# chicker.net
KiCad netlist of a schematic drawn in Altium Designer
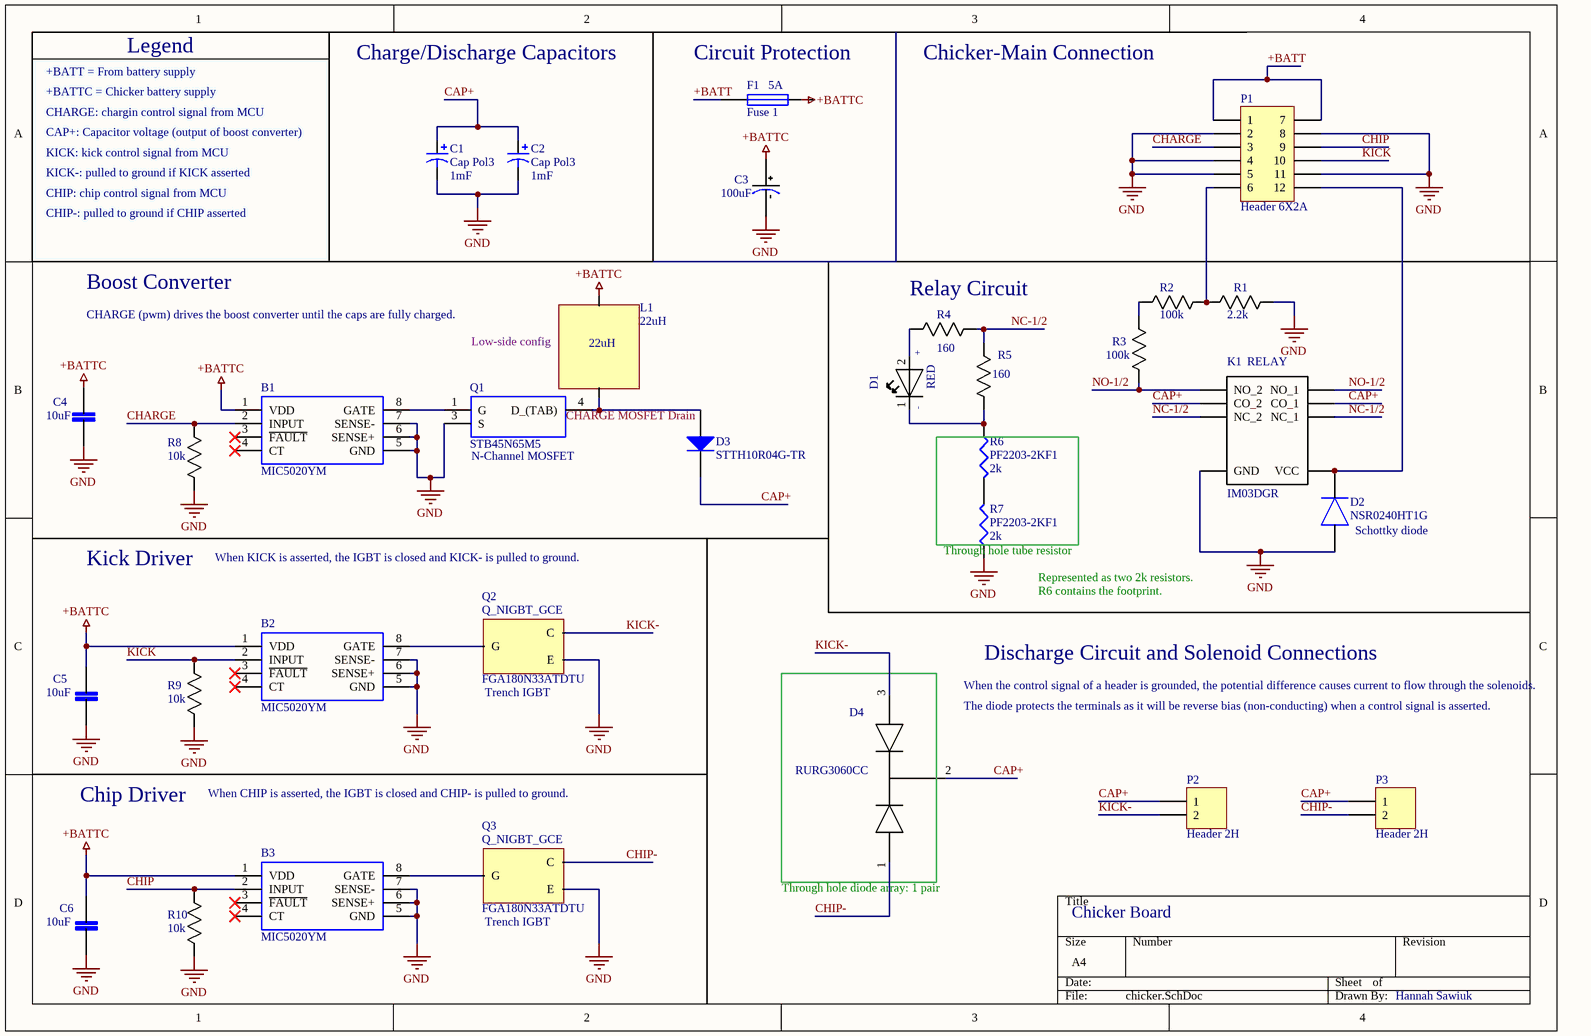
[diagram p0: chicker.SchDoc]

(export (version "E")
  (design (tool "Eeschema 10.0.6"))
  (components
    (comp (ref "B1")
      (value "MIC5020YM")
      (footprint "SOIC127P600X188-8N")
      (description "Low-Side Gate Driver IC Non-Inverting 8-SOIC")
      (fields (field (name "MP") "Microchip") (field (name "DIGI-KEY_PART_NUM") "576-1818-5-ND"))
      (libsource (lib "MIC5020YM") (part "MIC5020YM"))
    )
    (comp (ref "B2")
      (value "MIC5020YM")
      (footprint "SOIC127P600X188-8N")
      (description "Low-Side Gate Driver IC Non-Inverting 8-SOIC")
      (fields (field (name "MP") "Microchip") (field (name "DIGI-KEY_PART_NUM") "576-1818-5-ND"))
      (libsource (lib "MIC5020YM") (part "MIC5020YM"))
    )
    (comp (ref "B3")
      (value "MIC5020YM")
      (footprint "SOIC127P600X188-8N")
      (description "Low-Side Gate Driver IC Non-Inverting 8-SOIC")
      (fields (field (name "MP") "Microchip") (field (name "DIGI-KEY_PART_NUM") "576-1818-5-ND"))
      (libsource (lib "MIC5020YM") (part "MIC5020YM"))
    )
    (comp (ref "C1")
      (value "Cap Pol3")
      (footprint "C0805")
      (description "Polarized Capacitor (Surface Mount)")
      (fields
        (field (name "ALTIUM_VALUE") "1mF")
        (field (name "DIGI-KEY_PART_NUM") "565-2754-ND")
        (field (name "MF") "United Chemi-Con")
      )
      (libsource (lib "Miscellaneous Devices") (part "Cap Pol3"))
    )
    (comp (ref "C2")
      (value "Cap Pol3")
      (footprint "C0805")
      (description "Polarized Capacitor (Surface Mount)")
      (fields
        (field (name "ALTIUM_VALUE") "1mF")
        (field (name "DIGI-KEY_PART_NUM") "565-2754-ND")
        (field (name "MF") "United Chemi-Con")
      )
      (libsource (lib "Miscellaneous Devices") (part "Cap Pol3"))
    )
    (comp (ref "C3")
      (value "100uF")
      (footprint "CAPPRD350W60D800H1150B_ECA-1HM101(Primary)")
      (description "CAP ALUM 100UF 20% 50V RADIAL")
      (fields (field (name "MF") "Panasonic") (field (name "MP") "ECA-1HM101"))
      (libsource (lib "ECA-1HM101") (part "ECA-1HM101"))
    )
    (comp (ref "C4")
      (value "10uF")
      (footprint "CAPC3216X100N")
      (description "CAP CER 10UF 25V X5R 1206")
      (fields (field (name "MF") "Samsung") (field (name "MP") "CL31A106KAHNNNE"))
      (libsource (lib "") (part "CL31A226KOCLFNC_1"))
    )
    (comp (ref "C5")
      (value "10uF")
      (footprint "CAPC3216X100N")
      (description "CAP CER 10UF 25V X5R 1206")
      (fields (field (name "MF") "Samsung") (field (name "MP") "CL31A106KAHNNNE"))
      (libsource (lib "CL31A226KOCLFNC") (part "CL31A226KOCLFNC"))
    )
    (comp (ref "C6")
      (value "10uF")
      (footprint "CAPC3216X100N")
      (description "CAP CER 10UF 25V X5R 1206")
      (fields (field (name "MF") "Samsung") (field (name "MP") "CL31A106KAHNNNE"))
      (libsource (lib "CL31A226KOCLFNC") (part "CL31A226KOCLFNC"))
    )
    (comp (ref "D1")
      (value "RED")
      (footprint "WL-SMRW-1206-RECT")
      (description "LED RED CLEAR 1206 SMD")
      (fields (field (name "MF") "Lite-On Inc.") (field (name "MP") "LTST-C150CKT"))
      (libsource (lib "WL-SMRW") (part "WL-SMRW"))
    )
    (comp (ref "D2")
      (value "NSR0240HT1G")
      (footprint "SOD2512X110N")
      (description "SMT Schottky Diode, 40V dc 250mA, 3ns, 2-pin SOD-323")
      (fields (field (name "MF") "ON Semiconductor") (field (name "RS PART NUMBER") "7931024P"))
      (libsource (lib "NSR0240HT1G") (part "NSR0240HT1G"))
    )
    (comp (ref "D3")
      (value "STTH10R04G-TR")
      (footprint "DPAK508P1542X460-3N")
      (description "DIODE GEN PURP 400V 10A D2PAK")
      (fields (field (name "DIGI-KEY_PART_NUM") "497-7575-1-ND") (field (name "MF") "STMicroelectronics"))
      (libsource (lib "Miscellaneous Devices") (part "Diode 1N914"))
    )
    (comp (ref "D4")
      (value "RURG3060CC")
      (footprint "SOT93_TIP147(Primary)")
      (description "DIODE ARRAY GP 600V 30A TO247")
      (fields (field (name "DIGI-KEY_PART_NUM") "RURG3060CC-ND") (field (name "MF") "On Semiconductor"))
      (libsource (lib "Schematic Components") (part "RURG3060CC"))
    )
    (comp (ref "F1")
      (value "Fuse 1")
      (footprint "FUSM3216X140N")
      (description "FUSE BOARD MOUNT 5A 32VDC 1206")
      (fields (field (name "DIGI-KEY_PART_NUM") "F3539CT-ND") (field (name "MF") "Littelfuse Inc."))
      (libsource (lib "Miscellaneous Devices") (part "Fuse 1"))
    )
    (comp (ref "K1")
      (value "IM03DGR")
      (footprint "GULLWINGS")
      (description "Relay, Signal, Dpdt, 250vac, 220vdc, 5a")
      (fields
        (field (name "MF") "TE Connectivity")
        (field (name "ALTIUM_VALUE") "RELAY")
        (field (name "MOUSER_PART_NUM") "655-IM03DGR")
      )
      (libsource (lib "IM03DGR") (part "IM03DGR"))
    )
    (comp (ref "L1")
      (value "22uH")
      (footprint "PCBComponent_1")
      (libsource (lib "Schematic Components") (part "Inductor 22uH"))
    )
    (comp (ref "P1")
      (value "Header 6X2A")
      (footprint "HDR2X6_CEN")
      (description "Header, 6-Pin, Dual row")
      (fields
        (field (name "DIGI-KEY_PART_NUM") "S2011E-06-ND")
        (field (name "MF") "Sullins Connector Solutions")
        (field (name "PUBLISHER") "Altium Limited")
      )
      (libsource (lib "Miscellaneous Connectors") (part "Header 6X2A"))
    )
    (comp (ref "P2")
      (value "Header 2H")
      (footprint "HDR1X2H")
      (description "2 Positions Header Connector 0.100\" (2.54mm) Through Hole, Right Angle Tin")
      (fields (field (name "DIGI-KEY_PART_NUM") "WM4300-ND") (field (name "MF") "Molex, LLC"))
      (libsource (lib "Miscellaneous Connectors") (part "Header 2H"))
    )
    (comp (ref "P3")
      (value "Header 2H")
      (footprint "HDR1X2H")
      (description "2 Positions Header Connector 0.100\" (2.54mm) Through Hole, Right Angle Tin")
      (fields (field (name "DIGI-KEY_PART_NUM") "WM4300-ND") (field (name "MF") "Molex, LLC"))
      (libsource (lib "Miscellaneous Connectors") (part "Header 2H"))
    )
    (comp (ref "Q1")
      (value "STB45N65M5")
      (footprint "TO254P1542X460-3N")
      (description "MOSFET N CH 650V 35A D2PAK")
      (fields (field (name "MF") "STMicroelectronics") (field (name "DIGI-KEY_PART_NUM") "497-12940-1-ND"))
      (libsource (lib "STB45N65M5") (part "STB45N65M5"))
    )
    (comp (ref "Q2")
      (value "FGA180N33ATDTU")
      (footprint "TO-3PN_V_FDA69N25(Primary)")
      (description "IGBT Trench 330V 180A 390W Through Hole TO-3P")
      (fields (field (name "DIGI-KEY_PART_NUM") "FGA180N33ATDTU-ND") (field (name "MF") "ON Semiconductor"))
      (libsource (lib "Schematic Components") (part "FGA180N33ATDTU"))
    )
    (comp (ref "Q3")
      (value "FGA180N33ATDTU")
      (footprint "TO-3PN_V_FDA69N25(Primary)")
      (description "IGBT Trench 330V 180A 390W Through Hole TO-3P")
      (fields (field (name "DIGI-KEY_PART_NUM") "FGA180N33ATDTU-ND") (field (name "MF") "ON Semiconductor"))
      (libsource (lib "Schematic Components") (part "FGA180N33ATDTU"))
    )
    (comp (ref "R1")
      (value "2.2k")
      (footprint "RESC2013X65N")
      (description "RES SMD 2.2K OHM 1% 1/8W 0805")
      (fields (field (name "MP") "RC0805FR-072K2L") (field (name "MF") "Yageo"))
      (libsource (lib "RC0805FR-072K2L") (part "RC0805FR-072K2L"))
    )
    (comp (ref "R2")
      (value "100k")
      (footprint "RESC2013X65N")
      (description "RES SMD 100K OHM 1% 1/8W 0805")
      (fields (field (name "MP") "RC0805FR-07100KL") (field (name "MF") "Yageo"))
      (libsource (lib "RC0805FR-072K2L") (part "RC0805FR-072K2L"))
    )
    (comp (ref "R3")
      (value "100k")
      (footprint "RESC2013X65N")
      (description "RES SMD 100K OHM 1% 1/8W 0805")
      (fields (field (name "MP") "RC0805FR-07100KL") (field (name "MF") "Yageo"))
      (libsource (lib "RC0805FR-072K2L") (part "RC0805FR-072K2L"))
    )
    (comp (ref "R4")
      (value "160")
      (footprint "RESC2013X65N")
      (description "RES SMD 160 OHM 1% 1/8W 0805")
      (fields (field (name "MP") "RC0805FR-07160RL") (field (name "MF") "Yageo"))
      (libsource (lib "RC0805FR-072K2L") (part "RC0805FR-072K2L"))
    )
    (comp (ref "R5")
      (value "160")
      (footprint "RESC2013X65N")
      (description "RES SMD 160 OHM 1% 1/8W 0805")
      (fields (field (name "MP") "RC0805FR-07160RL") (field (name "MF") "Yageo"))
      (libsource (lib "RC0805FR-072K2L") (part "RC0805FR-072K2L"))
    )
    (comp (ref "R6")
      (value "PF2203-2KF1")
      (footprint "POWER_DIODE")
      (description "RES 2K OHM 35W 1% TO220")
      (fields
        (field (name "ALTIUM_VALUE") "2k")
        (field (name "DIGI-KEY_PART_NUM") "696-1170-ND")
        (field (name "MF") "Riedon")
        (field (name "PUBLISHER") "Altium Limited")
      )
      (libsource (lib "Miscellaneous Devices") (part "Res3"))
    )
    (comp (ref "R7")
      (value "PF2203-2KF1")
      (description "RES 2K OHM 35W 1% TO220")
      (fields
        (field (name "ALTIUM_VALUE") "2k")
        (field (name "DIGI-KEY_PART_NUM") "696-1170-ND")
        (field (name "MF") "Riedon")
        (field (name "PUBLISHER") "Altium Limited")
      )
      (libsource (lib "Miscellaneous Devices") (part "Res3"))
    )
    (comp (ref "R8")
      (value "10k")
      (footprint "RESC2013X65N")
      (description "RES SMD 10K OHM 1% 1/8W 0805")
      (fields (field (name "MP") "RC0805FR-0710KL") (field (name "MF") "Yageo"))
      (libsource (lib "RC0805FR-072K2L") (part "RC0805FR-072K2L"))
    )
    (comp (ref "R9")
      (value "10k")
      (footprint "RESC2013X65N")
      (description "RES SMD 10K OHM 1% 1/8W 0805")
      (fields (field (name "MP") "RC0805FR-0710KL") (field (name "MF") "Yageo"))
      (libsource (lib "RC0805FR-072K2L") (part "RC0805FR-072K2L"))
    )
    (comp (ref "R10")
      (value "10k")
      (footprint "RESC2013X65N")
      (description "RES SMD 10K OHM 1% 1/8W 0805")
      (fields (field (name "MP") "RC0805FR-0710KL") (field (name "MF") "Yageo"))
      (libsource (lib "RC0805FR-072K2L") (part "RC0805FR-072K2L"))
    )
  )
  (nets
    (net (code "1") (name "+BATTC") (class "Default")
      (node (ref "B1") (pin "1") (pinfunction "VDD_1") (pintype "power_in"))
      (node (ref "B2") (pin "1") (pinfunction "VDD_1") (pintype "power_in"))
      (node (ref "B3") (pin "1") (pinfunction "VDD_1") (pintype "power_in"))
      (node (ref "C3") (pin "POS") (pinfunction "POS_POS") (pintype "passive"))
      (node (ref "C4") (pin "1") (pinfunction "1_1") (pintype "passive"))
      (node (ref "C5") (pin "1") (pinfunction "1_1") (pintype "passive"))
      (node (ref "C6") (pin "1") (pinfunction "1_1") (pintype "passive"))
      (node (ref "L1") (pin "1") (pinfunction "1_1") (pintype "passive"))
    )
    (net (code "2") (name "/+BATT") (class "Default")
      (node (ref "F1") (pin "2") (pinfunction "2_2") (pintype "passive"))
      (node (ref "P1") (pin "1") (pinfunction "1_1") (pintype "passive"))
      (node (ref "P1") (pin "7") (pinfunction "7_7") (pintype "passive"))
    )
    (net (code "3") (name "/CAP+") (class "Default")
      (node (ref "C1") (pin "1") (pinfunction "1_1") (pintype "passive"))
      (node (ref "C2") (pin "1") (pinfunction "1_1") (pintype "passive"))
      (node (ref "D3") (pin "2") (pinfunction "K_2") (pintype "passive"))
      (node (ref "D4") (pin "2") (pinfunction "6_2") (pintype "passive"))
      (node (ref "K1") (pin "3") (pinfunction "CO_1_3") (pintype "passive"))
      (node (ref "K1") (pin "6") (pinfunction "CO_2_6") (pintype "passive"))
      (node (ref "P2") (pin "1") (pinfunction "1_1") (pintype "passive"))
      (node (ref "P3") (pin "1") (pinfunction "1_1") (pintype "passive"))
    )
    (net (code "4") (name "/CHARGE") (class "Default")
      (node (ref "B1") (pin "2") (pinfunction "INPUT_2") (pintype "passive"))
      (node (ref "P1") (pin "3") (pinfunction "3_3") (pintype "passive"))
      (node (ref "R8") (pin "1") (pinfunction "R1_1") (pintype "passive"))
    )
    (net (code "5") (name "/CHIP") (class "Default")
      (node (ref "B3") (pin "2") (pinfunction "INPUT_2") (pintype "passive"))
      (node (ref "P1") (pin "9") (pinfunction "9_9") (pintype "passive"))
      (node (ref "R10") (pin "1") (pinfunction "R1_1") (pintype "passive"))
    )
    (net (code "6") (name "/CHIP-") (class "Default")
      (node (ref "D4") (pin "1") (pinfunction "7_1") (pintype "passive"))
      (node (ref "P3") (pin "2") (pinfunction "2_2") (pintype "passive"))
      (node (ref "Q3") (pin "4") (pinfunction "C_4") (pintype "passive"))
    )
    (net (code "7") (name "/KICK") (class "Default")
      (node (ref "B2") (pin "2") (pinfunction "INPUT_2") (pintype "passive"))
      (node (ref "P1") (pin "10") (pinfunction "10_10") (pintype "passive"))
      (node (ref "R9") (pin "1") (pinfunction "R1_1") (pintype "passive"))
    )
    (net (code "8") (name "/KICK-") (class "Default")
      (node (ref "D4") (pin "3") (pinfunction "1_3") (pintype "passive"))
      (node (ref "P2") (pin "2") (pinfunction "2_2") (pintype "passive"))
      (node (ref "Q2") (pin "4") (pinfunction "C_4") (pintype "passive"))
    )
    (net (code "9") (name "/NC-1{slash}2") (class "Default")
      (node (ref "K1") (pin "2") (pinfunction "NC_1_2") (pintype "passive"))
      (node (ref "K1") (pin "7") (pinfunction "NC_2_7") (pintype "passive"))
      (node (ref "R4") (pin "1") (pinfunction "R1_1") (pintype "passive"))
      (node (ref "R5") (pin "2") (pinfunction "R2_2") (pintype "passive"))
    )
    (net (code "10") (name "/NO-1{slash}2") (class "Default")
      (node (ref "K1") (pin "4") (pinfunction "NO_1_4") (pintype "passive"))
      (node (ref "K1") (pin "5") (pinfunction "NO_2_5") (pintype "passive"))
      (node (ref "R3") (pin "1") (pinfunction "R1_1") (pintype "passive"))
    )
    (net (code "11") (name "GND") (class "Default")
      (node (ref "B1") (pin "5") (pinfunction "GND_5") (pintype "passive"))
      (node (ref "B1") (pin "6") (pinfunction "SENSE+_6") (pintype "passive"))
      (node (ref "B1") (pin "7") (pinfunction "SENSE-_7") (pintype "passive"))
      (node (ref "B2") (pin "5") (pinfunction "GND_5") (pintype "passive"))
      (node (ref "B2") (pin "6") (pinfunction "SENSE+_6") (pintype "passive"))
      (node (ref "B2") (pin "7") (pinfunction "SENSE-_7") (pintype "passive"))
      (node (ref "B3") (pin "5") (pinfunction "GND_5") (pintype "passive"))
      (node (ref "B3") (pin "6") (pinfunction "SENSE+_6") (pintype "passive"))
      (node (ref "B3") (pin "7") (pinfunction "SENSE-_7") (pintype "passive"))
      (node (ref "C1") (pin "2") (pinfunction "2_2") (pintype "passive"))
      (node (ref "C2") (pin "2") (pinfunction "2_2") (pintype "passive"))
      (node (ref "C3") (pin "NEG") (pinfunction "NEG_NEG") (pintype "passive"))
      (node (ref "C4") (pin "2") (pinfunction "2_2") (pintype "passive"))
      (node (ref "C5") (pin "2") (pinfunction "2_2") (pintype "passive"))
      (node (ref "C6") (pin "2") (pinfunction "2_2") (pintype "passive"))
      (node (ref "D2") (pin "2") (pinfunction "A_2") (pintype "passive"))
      (node (ref "K1") (pin "8") (pinfunction "GND_8") (pintype "power_in"))
      (node (ref "P1") (pin "11") (pinfunction "11_11") (pintype "passive"))
      (node (ref "P1") (pin "2") (pinfunction "2_2") (pintype "passive"))
      (node (ref "P1") (pin "4") (pinfunction "4_4") (pintype "passive"))
      (node (ref "P1") (pin "5") (pinfunction "5_5") (pintype "passive"))
      (node (ref "P1") (pin "8") (pinfunction "8_8") (pintype "passive"))
      (node (ref "Q1") (pin "3") (pinfunction "S_3") (pintype "passive"))
      (node (ref "Q2") (pin "3") (pinfunction "E_3") (pintype "passive"))
      (node (ref "Q3") (pin "3") (pinfunction "E_3") (pintype "passive"))
      (node (ref "R1") (pin "1") (pinfunction "R1_1") (pintype "passive"))
      (node (ref "R10") (pin "2") (pinfunction "R2_2") (pintype "passive"))
      (node (ref "R7") (pin "1") (pinfunction "1_1") (pintype "passive"))
      (node (ref "R8") (pin "2") (pinfunction "R2_2") (pintype "passive"))
      (node (ref "R9") (pin "2") (pinfunction "R2_2") (pintype "passive"))
    )
    (net (code "12") (name "Net-(B1-GATE)") (class "Default")
      (node (ref "B1") (pin "8") (pinfunction "GATE_8") (pintype "passive"))
      (node (ref "Q1") (pin "1") (pinfunction "G_1") (pintype "passive"))
    )
    (net (code "13") (name "Net-(B2-GATE)") (class "Default")
      (node (ref "B2") (pin "8") (pinfunction "GATE_8") (pintype "passive"))
      (node (ref "Q2") (pin "G") (pinfunction "G_G") (pintype "passive"))
    )
    (net (code "14") (name "Net-(B3-GATE)") (class "Default")
      (node (ref "B3") (pin "8") (pinfunction "GATE_8") (pintype "passive"))
      (node (ref "Q3") (pin "G") (pinfunction "G_G") (pintype "passive"))
    )
    (net (code "15") (name "Net-(D1-NEG)") (class "Default")
      (node (ref "D1") (pin "1") (pinfunction "NEG_1") (pintype "bidirectional"))
      (node (ref "R5") (pin "1") (pinfunction "R1_1") (pintype "passive"))
      (node (ref "R6") (pin "1") (pinfunction "1_1") (pintype "passive"))
    )
    (net (code "16") (name "Net-(D1-POS)") (class "Default")
      (node (ref "D1") (pin "2") (pinfunction "POS_2") (pintype "bidirectional"))
      (node (ref "R4") (pin "2") (pinfunction "R2_2") (pintype "passive"))
    )
    (net (code "17") (name "Net-(D2-K)") (class "Default")
      (node (ref "D2") (pin "1") (pinfunction "K_1") (pintype "passive"))
      (node (ref "K1") (pin "1") (pinfunction "VCC_1") (pintype "power_in"))
      (node (ref "P1") (pin "12") (pinfunction "12_12") (pintype "passive"))
    )
    (net (code "18") (name "Net-(D3-A)") (class "Default")
      (node (ref "D3") (pin "1") (pinfunction "A_1") (pintype "passive"))
      (node (ref "L1") (pin "0") (pinfunction "0_0") (pintype "passive"))
      (node (ref "Q1") (pin "4") (pinfunction "D_(TAB)_4") (pintype "passive"))
    )
    (net (code "19") (name "Net-(R1-R2)") (class "Default")
      (node (ref "P1") (pin "6") (pinfunction "6_6") (pintype "passive"))
      (node (ref "R1") (pin "2") (pinfunction "R2_2") (pintype "passive"))
      (node (ref "R2") (pin "2") (pinfunction "R2_2") (pintype "passive"))
    )
    (net (code "20") (name "Net-(R2-R1)") (class "Default")
      (node (ref "R2") (pin "1") (pinfunction "R1_1") (pintype "passive"))
      (node (ref "R3") (pin "2") (pinfunction "R2_2") (pintype "passive"))
    )
    (net (code "21") (name "Net-(R6-Pad2)") (class "Default")
      (node (ref "R6") (pin "2") (pinfunction "2_2") (pintype "passive"))
      (node (ref "R7") (pin "2") (pinfunction "2_2") (pintype "passive"))
    )
    (net (code "22") (name "unconnected-(B1-CT-Pad4)") (class "Default")
      (node (ref "B1") (pin "4") (pinfunction "CT_4") (pintype "passive+no_connect"))
    )
    (net (code "23") (name "unconnected-(B1-FAULT-Pad3)") (class "Default")
      (node (ref "B1") (pin "3") (pinfunction "FAULT_3") (pintype "passive+no_connect"))
    )
    (net (code "24") (name "unconnected-(B2-CT-Pad4)") (class "Default")
      (node (ref "B2") (pin "4") (pinfunction "CT_4") (pintype "passive+no_connect"))
    )
    (net (code "25") (name "unconnected-(B2-FAULT-Pad3)") (class "Default")
      (node (ref "B2") (pin "3") (pinfunction "FAULT_3") (pintype "passive+no_connect"))
    )
    (net (code "26") (name "unconnected-(B3-CT-Pad4)") (class "Default")
      (node (ref "B3") (pin "4") (pinfunction "CT_4") (pintype "passive+no_connect"))
    )
    (net (code "27") (name "unconnected-(B3-FAULT-Pad3)") (class "Default")
      (node (ref "B3") (pin "3") (pinfunction "FAULT_3") (pintype "passive+no_connect"))
    )
    (net (code "28") (name "unconnected-(F1-Pad1)") (class "Default")
      (node (ref "F1") (pin "1") (pinfunction "1_1") (pintype "passive"))
    )
  )
)
